# sensor.net
KiCad netlist of a schematic drawn in EAGLE
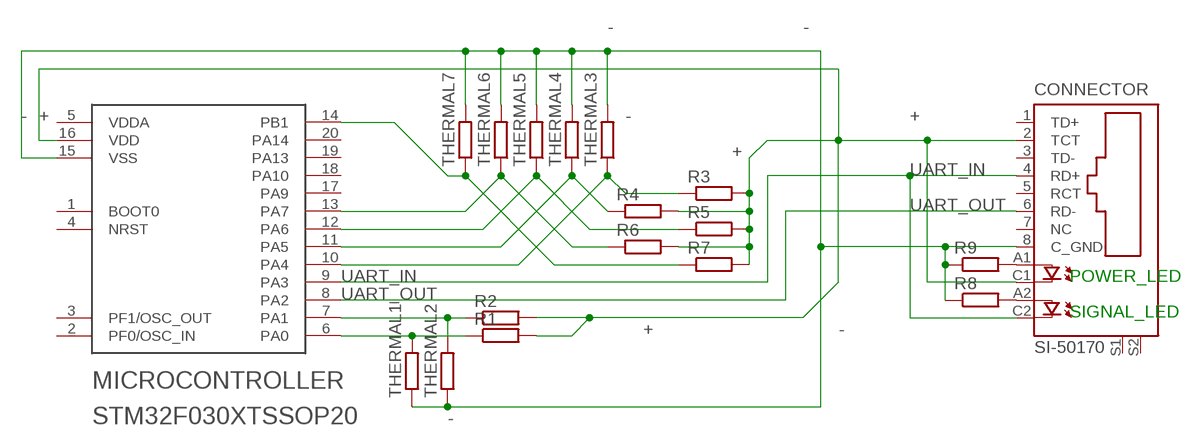
[diagram p0: schematic, sheet 1]

(export (version "E")
  (design (tool "Eeschema 10.0.6"))
  (components
    (comp (ref "CONNECTOR")
      (value "SI-50170")
      (footprint "eagle-import:SI-50170")
      (libsource (lib "eagle-import") (part "SI-50170"))
    )
    (comp (ref "MICROCONTROLLER")
      (value "STM32F030XTSSOP20")
      (footprint "eagle-import:TSSOP-20")
      (libsource (lib "eagle-import") (part "STM32F030XTSSOP20"))
    )
    (comp (ref "R1")
      (value "R-EU_0204/5")
      (footprint "eagle-import:0204_5")
      (libsource (lib "eagle-import") (part "R-EU_0204/5"))
    )
    (comp (ref "R2")
      (value "R-EU_0204/5")
      (footprint "eagle-import:0204_5")
      (libsource (lib "eagle-import") (part "R-EU_0204/5"))
    )
    (comp (ref "R3")
      (value "R-EU_0204/5")
      (footprint "eagle-import:0204_5")
      (libsource (lib "eagle-import") (part "R-EU_0204/5"))
    )
    (comp (ref "R4")
      (value "R-EU_0204/5")
      (footprint "eagle-import:0204_5")
      (libsource (lib "eagle-import") (part "R-EU_0204/5"))
    )
    (comp (ref "R5")
      (value "R-EU_0204/5")
      (footprint "eagle-import:0204_5")
      (libsource (lib "eagle-import") (part "R-EU_0204/5"))
    )
    (comp (ref "R6")
      (value "R-EU_0204/5")
      (footprint "eagle-import:0204_5")
      (libsource (lib "eagle-import") (part "R-EU_0204/5"))
    )
    (comp (ref "R7")
      (value "R-EU_0204/5")
      (footprint "eagle-import:0204_5")
      (libsource (lib "eagle-import") (part "R-EU_0204/5"))
    )
    (comp (ref "R8")
      (value "R-EU_0204/5")
      (footprint "eagle-import:0204_5")
      (libsource (lib "eagle-import") (part "R-EU_0204/5"))
    )
    (comp (ref "R9")
      (value "R-EU_0204/5")
      (footprint "eagle-import:0204_5")
      (libsource (lib "eagle-import") (part "R-EU_0204/5"))
    )
    (comp (ref "THERMAL1")
      (value "R-EU_V526-0")
      (footprint "eagle-import:V526-0")
      (libsource (lib "eagle-import") (part "R-EU_V526-0"))
    )
    (comp (ref "THERMAL2")
      (value "R-EU_V526-0")
      (footprint "eagle-import:V526-0")
      (libsource (lib "eagle-import") (part "R-EU_V526-0"))
    )
    (comp (ref "THERMAL3")
      (value "R-EU_V526-0")
      (footprint "eagle-import:V526-0")
      (libsource (lib "eagle-import") (part "R-EU_V526-0"))
    )
    (comp (ref "THERMAL4")
      (value "R-EU_V526-0")
      (footprint "eagle-import:V526-0")
      (libsource (lib "eagle-import") (part "R-EU_V526-0"))
    )
    (comp (ref "THERMAL5")
      (value "R-EU_V526-0")
      (footprint "eagle-import:V526-0")
      (libsource (lib "eagle-import") (part "R-EU_V526-0"))
    )
    (comp (ref "THERMAL6")
      (value "R-EU_V526-0")
      (footprint "eagle-import:V526-0")
      (libsource (lib "eagle-import") (part "R-EU_V526-0"))
    )
    (comp (ref "THERMAL7")
      (value "R-EU_V526-0")
      (footprint "eagle-import:V526-0")
      (libsource (lib "eagle-import") (part "R-EU_V526-0"))
    )
  )
  (nets
    (net (code "1") (name "/+") (class "Default")
      (node (ref "CONNECTOR") (pin "2") (pinfunction "TCT_2") (pintype "passive"))
      (node (ref "CONNECTOR") (pin "C1") (pinfunction "C_C1") (pintype "passive"))
      (node (ref "MICROCONTROLLER") (pin "16") (pinfunction "VDD_16") (pintype "bidirectional"))
      (node (ref "R1") (pin "2") (pinfunction "2_2") (pintype "passive"))
      (node (ref "R2") (pin "2") (pinfunction "2_2") (pintype "passive"))
      (node (ref "R3") (pin "2") (pinfunction "2_2") (pintype "passive"))
      (node (ref "R4") (pin "2") (pinfunction "2_2") (pintype "passive"))
      (node (ref "R5") (pin "2") (pinfunction "2_2") (pintype "passive"))
      (node (ref "R6") (pin "2") (pinfunction "2_2") (pintype "passive"))
      (node (ref "R7") (pin "2") (pinfunction "2_2") (pintype "passive"))
    )
    (net (code "2") (name "/-") (class "Default")
      (node (ref "CONNECTOR") (pin "8") (pinfunction "C_GND_8") (pintype "passive"))
      (node (ref "MICROCONTROLLER") (pin "15") (pinfunction "VSS_15") (pintype "bidirectional"))
      (node (ref "R8") (pin "1") (pinfunction "1_1") (pintype "passive"))
      (node (ref "R9") (pin "1") (pinfunction "1_1") (pintype "passive"))
      (node (ref "THERMAL1") (pin "1") (pinfunction "1_1") (pintype "passive"))
      (node (ref "THERMAL2") (pin "1") (pinfunction "1_1") (pintype "passive"))
      (node (ref "THERMAL3") (pin "2") (pinfunction "2_2") (pintype "passive"))
      (node (ref "THERMAL4") (pin "2") (pinfunction "2_2") (pintype "passive"))
      (node (ref "THERMAL5") (pin "2") (pinfunction "2_2") (pintype "passive"))
      (node (ref "THERMAL6") (pin "2") (pinfunction "2_2") (pintype "passive"))
      (node (ref "THERMAL7") (pin "2") (pinfunction "2_2") (pintype "passive"))
    )
    (net (code "3") (name "/UART_IN") (class "Default")
      (node (ref "CONNECTOR") (pin "4") (pinfunction "RD+_4") (pintype "passive"))
      (node (ref "CONNECTOR") (pin "C2") (pinfunction "C1_C2") (pintype "passive"))
      (node (ref "MICROCONTROLLER") (pin "9") (pinfunction "PA3_9") (pintype "bidirectional"))
    )
    (net (code "4") (name "/UART_OUT") (class "Default")
      (node (ref "CONNECTOR") (pin "6") (pinfunction "RD-_6") (pintype "passive"))
      (node (ref "MICROCONTROLLER") (pin "8") (pinfunction "PA2_8") (pintype "bidirectional"))
    )
    (net (code "5") (name "Net-(CONNECTOR-A)") (class "Default")
      (node (ref "CONNECTOR") (pin "A1") (pinfunction "A_A1") (pintype "passive"))
      (node (ref "R9") (pin "2") (pinfunction "2_2") (pintype "passive"))
    )
    (net (code "6") (name "Net-(CONNECTOR-A1)") (class "Default")
      (node (ref "CONNECTOR") (pin "A2") (pinfunction "A1_A2") (pintype "passive"))
      (node (ref "R8") (pin "2") (pinfunction "2_2") (pintype "passive"))
    )
    (net (code "7") (name "Net-(MICROCONTROLLER-PA0)") (class "Default")
      (node (ref "MICROCONTROLLER") (pin "6") (pinfunction "PA0_6") (pintype "bidirectional"))
      (node (ref "R1") (pin "1") (pinfunction "1_1") (pintype "passive"))
      (node (ref "THERMAL1") (pin "2") (pinfunction "2_2") (pintype "passive"))
    )
    (net (code "8") (name "Net-(MICROCONTROLLER-PA1)") (class "Default")
      (node (ref "MICROCONTROLLER") (pin "7") (pinfunction "PA1_7") (pintype "bidirectional"))
      (node (ref "R2") (pin "1") (pinfunction "1_1") (pintype "passive"))
      (node (ref "THERMAL2") (pin "2") (pinfunction "2_2") (pintype "passive"))
    )
    (net (code "9") (name "Net-(MICROCONTROLLER-PA4)") (class "Default")
      (node (ref "MICROCONTROLLER") (pin "10") (pinfunction "PA4_10") (pintype "bidirectional"))
      (node (ref "R3") (pin "1") (pinfunction "1_1") (pintype "passive"))
      (node (ref "THERMAL3") (pin "1") (pinfunction "1_1") (pintype "passive"))
    )
    (net (code "10") (name "Net-(MICROCONTROLLER-PA5)") (class "Default")
      (node (ref "MICROCONTROLLER") (pin "11") (pinfunction "PA5_11") (pintype "bidirectional"))
      (node (ref "R4") (pin "1") (pinfunction "1_1") (pintype "passive"))
      (node (ref "THERMAL4") (pin "1") (pinfunction "1_1") (pintype "passive"))
    )
    (net (code "11") (name "Net-(MICROCONTROLLER-PA6)") (class "Default")
      (node (ref "MICROCONTROLLER") (pin "12") (pinfunction "PA6_12") (pintype "bidirectional"))
      (node (ref "R5") (pin "1") (pinfunction "1_1") (pintype "passive"))
      (node (ref "THERMAL5") (pin "1") (pinfunction "1_1") (pintype "passive"))
    )
    (net (code "12") (name "Net-(MICROCONTROLLER-PA7)") (class "Default")
      (node (ref "MICROCONTROLLER") (pin "13") (pinfunction "PA7_13") (pintype "bidirectional"))
      (node (ref "R6") (pin "1") (pinfunction "1_1") (pintype "passive"))
      (node (ref "THERMAL6") (pin "1") (pinfunction "1_1") (pintype "passive"))
    )
    (net (code "13") (name "Net-(MICROCONTROLLER-PB1)") (class "Default")
      (node (ref "MICROCONTROLLER") (pin "14") (pinfunction "PB1_14") (pintype "bidirectional"))
      (node (ref "R7") (pin "1") (pinfunction "1_1") (pintype "passive"))
      (node (ref "THERMAL7") (pin "1") (pinfunction "1_1") (pintype "passive"))
    )
    (net (code "14") (name "unconnected-(CONNECTOR-NC-Pad7)") (class "Default")
      (node (ref "CONNECTOR") (pin "7") (pinfunction "NC_7") (pintype "passive"))
    )
    (net (code "15") (name "unconnected-(CONNECTOR-PadS1)") (class "Default")
      (node (ref "CONNECTOR") (pin "S1") (pinfunction "S1_S1") (pintype "passive"))
    )
    (net (code "16") (name "unconnected-(CONNECTOR-PadS2)") (class "Default")
      (node (ref "CONNECTOR") (pin "S2") (pinfunction "S2_S2") (pintype "passive"))
    )
    (net (code "17") (name "unconnected-(CONNECTOR-RCT-Pad5)") (class "Default")
      (node (ref "CONNECTOR") (pin "5") (pinfunction "RCT_5") (pintype "passive"))
    )
    (net (code "18") (name "unconnected-(CONNECTOR-TD+-Pad1)") (class "Default")
      (node (ref "CONNECTOR") (pin "1") (pinfunction "TD+_1") (pintype "passive"))
    )
    (net (code "19") (name "unconnected-(CONNECTOR-TD--Pad3)") (class "Default")
      (node (ref "CONNECTOR") (pin "3") (pinfunction "TD-_3") (pintype "passive"))
    )
    (net (code "20") (name "unconnected-(MICROCONTROLLER-BOOT0-Pad1)") (class "Default")
      (node (ref "MICROCONTROLLER") (pin "1") (pinfunction "BOOT0_1") (pintype "bidirectional"))
    )
    (net (code "21") (name "unconnected-(MICROCONTROLLER-NRST-Pad4)") (class "Default")
      (node (ref "MICROCONTROLLER") (pin "4") (pinfunction "NRST_4") (pintype "bidirectional"))
    )
    (net (code "22") (name "unconnected-(MICROCONTROLLER-PA9-Pad17)") (class "Default")
      (node (ref "MICROCONTROLLER") (pin "17") (pinfunction "PA9_17") (pintype "bidirectional"))
    )
    (net (code "23") (name "unconnected-(MICROCONTROLLER-PA10-Pad18)") (class "Default")
      (node (ref "MICROCONTROLLER") (pin "18") (pinfunction "PA10_18") (pintype "bidirectional"))
    )
    (net (code "24") (name "unconnected-(MICROCONTROLLER-PA13-Pad19)") (class "Default")
      (node (ref "MICROCONTROLLER") (pin "19") (pinfunction "PA13_19") (pintype "bidirectional"))
    )
    (net (code "25") (name "unconnected-(MICROCONTROLLER-PA14-Pad20)") (class "Default")
      (node (ref "MICROCONTROLLER") (pin "20") (pinfunction "PA14_20") (pintype "bidirectional"))
    )
    (net (code "26") (name "unconnected-(MICROCONTROLLER-PF0{slash}OSC_IN-Pad2)") (class "Default")
      (node (ref "MICROCONTROLLER") (pin "2") (pinfunction "PF0/OSC_IN_2") (pintype "bidirectional"))
    )
    (net (code "27") (name "unconnected-(MICROCONTROLLER-PF1{slash}OSC_OUT-Pad3)") (class "Default")
      (node (ref "MICROCONTROLLER") (pin "3") (pinfunction "PF1/OSC_OUT_3") (pintype "bidirectional"))
    )
    (net (code "28") (name "unconnected-(MICROCONTROLLER-VDDA-Pad5)") (class "Default")
      (node (ref "MICROCONTROLLER") (pin "5") (pinfunction "VDDA_5") (pintype "bidirectional"))
    )
  )
)
